# Nestling_2_1_EXB_WIFI_ESP8266EX.net
KiCad netlist of a schematic drawn in Altium Designer
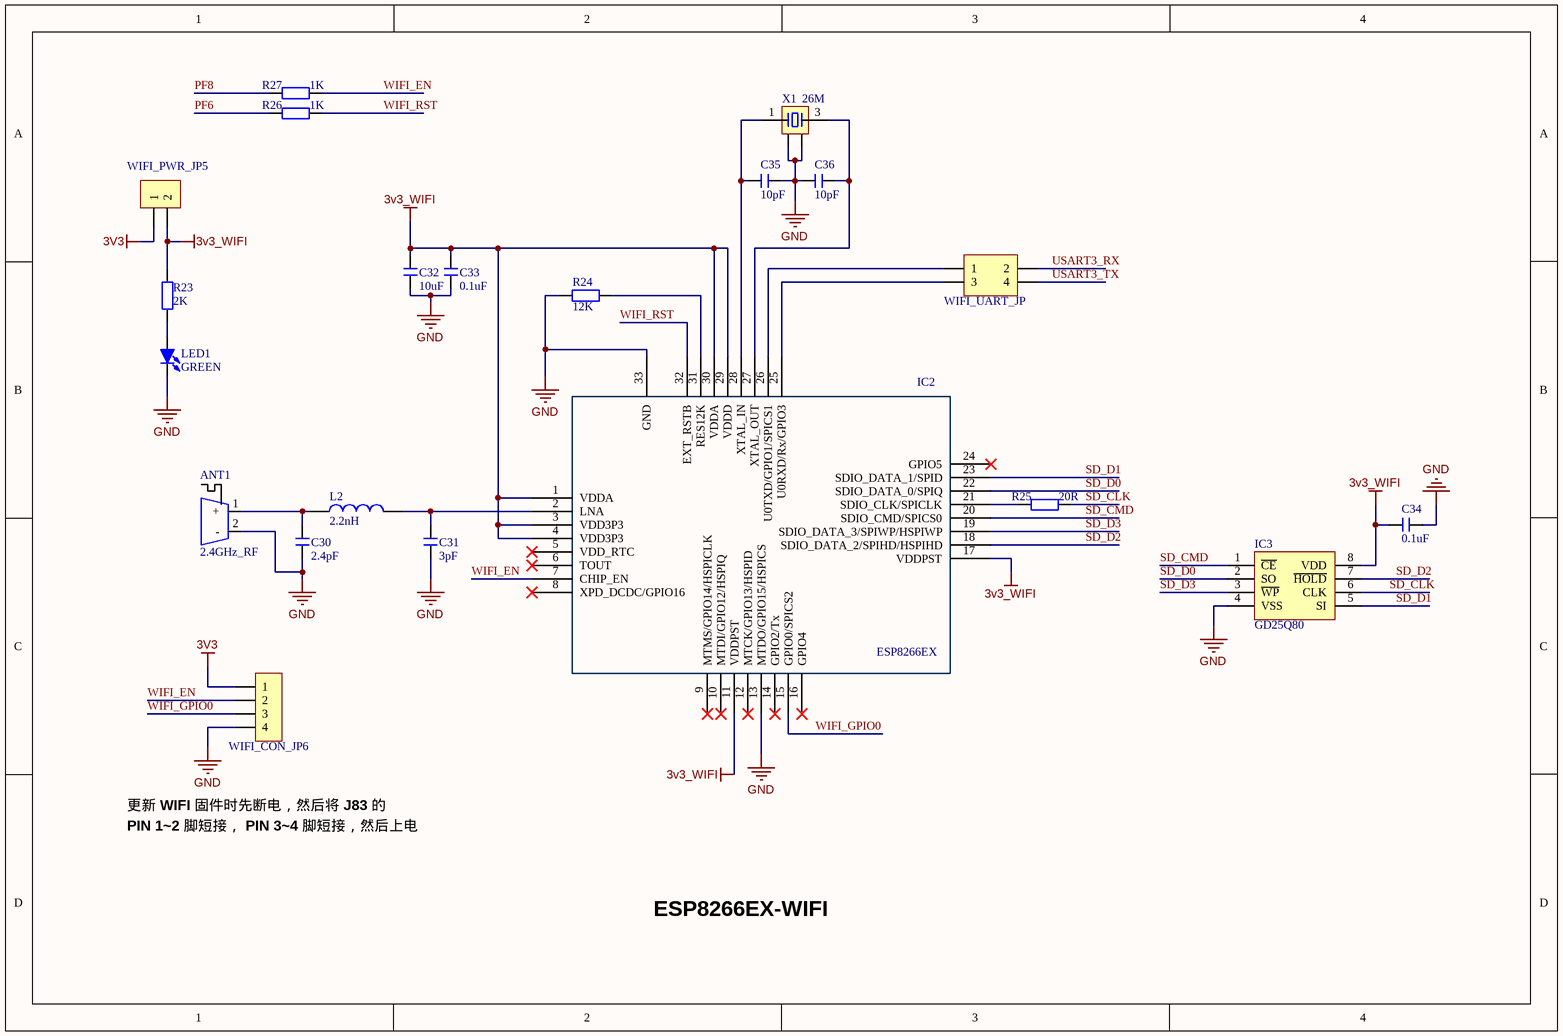
[diagram p0: Nestling_2.1_EXB_WIFI_ESP8266EX.SchDoc]

(export (version "E")
  (design (tool "Eeschema 10.0.6"))
  (components
    (comp (ref "ANT1")
      (value "2.4GHz_RF")
      (footprint "ANT-F-1-2.4G")
      (libsource (lib "altium-import") (part "root_0_2.4GHz_RF_"))
    )
    (comp (ref "C30")
      (value "2.4pF")
      (footprint "C 0603_M")
      (description "无极性贴片电容")
      (fields (field (name "版权归属") "源创客"))
      (libsource (lib "altium-import") (part "root_3_C_"))
    )
    (comp (ref "C31")
      (value "3pF")
      (footprint "C 0603_M")
      (description "无极性贴片电容")
      (fields (field (name "版权归属") "源创客"))
      (libsource (lib "altium-import") (part "root_3_C_"))
    )
    (comp (ref "C32")
      (value "10uF")
      (footprint "C 0603_M")
      (description "无极性贴片电容")
      (fields (field (name "版权归属") "源创客"))
      (libsource (lib "altium-import") (part "root_3_C_"))
    )
    (comp (ref "C33")
      (value "0.1uF")
      (footprint "C 0603_M")
      (description "无极性贴片电容")
      (fields (field (name "版权归属") "源创客"))
      (libsource (lib "altium-import") (part "root_3_C_"))
    )
    (comp (ref "C34")
      (value "0.1uF")
      (footprint "C 0603_M")
      (description "无极性贴片电容")
      (fields (field (name "版权归属") "源创客"))
      (libsource (lib "altium-import") (part "root_0_C_"))
    )
    (comp (ref "C35")
      (value "10pF")
      (footprint "C 0603_M")
      (description "无极性贴片电容")
      (fields (field (name "版权归属") "源创客"))
      (libsource (lib "altium-import") (part "root_2_C_"))
    )
    (comp (ref "C36")
      (value "10pF")
      (footprint "C 0603_M")
      (description "无极性贴片电容")
      (fields (field (name "版权归属") "源创客"))
      (libsource (lib "altium-import") (part "root_2_C_"))
    )
    (comp (ref "IC2")
      (value "ESP8266EX")
      (footprint "QFN32 5x5_L")
      (description "WIFI-芯片")
      (fields (field (name "版权归属") "源创客"))
      (libsource (lib "altium-import") (part "root_0_ESP8266EX_"))
    )
    (comp (ref "IC3")
      (value "GD25Q80")
      (footprint "SOP8W_N")
      (description "外置Flash")
      (fields (field (name "版权归属") "源创客"))
      (libsource (lib "altium-import") (part "root_0_SST25VFxx_"))
    )
    (comp (ref "L2")
      (value "2.2nH")
      (footprint "L 0603")
      (description "小功率贴片电感")
      (fields (field (name "版权归属") "源创客"))
      (libsource (lib "altium-import") (part "root_0_L_"))
    )
    (comp (ref "LED1")
      (value "GREEN")
      (footprint "LED 0603G")
      (description "贴片LED")
      (fields (field (name "版权归属") "源创客"))
      (libsource (lib "altium-import") (part "root_0_LED-SMD_"))
    )
    (comp (ref "R23")
      (value "2K")
      (footprint "R 0603_M")
      (description "Resistor")
      (libsource (lib "") (part "RES_1"))
    )
    (comp (ref "R24")
      (value "12K")
      (footprint "R 0603_M")
      (description "Resistor")
      (libsource (lib "General") (part "RES"))
    )
    (comp (ref "R25")
      (value "20R")
      (footprint "R 0603_M")
      (description "Resistor")
      (libsource (lib "General") (part "RES"))
    )
    (comp (ref "R26")
      (value "1K")
      (footprint "R 0603_M")
      (description "Resistor")
      (libsource (lib "General") (part "RES"))
    )
    (comp (ref "R27")
      (value "1K")
      (footprint "R 0603_M")
      (description "Resistor")
      (libsource (lib "General") (part "RES"))
    )
    (comp (ref "WIFI_CON_JP6")
      (value "HDR-1X4")
      (footprint "HDR2.54-LI-4P")
      (description "4P接插件")
      (fields (field (name "版权归属") "源创客"))
      (libsource (lib "altium-import") (part "root_0_Header 4_"))
    )
    (comp (ref "WIFI_PWR_JP5")
      (value "HDR-1X2")
      (footprint "HDR2.54-LI-2P")
      (description "2P接插件")
      (fields (field (name "版权归属") "源创客"))
      (libsource (lib "altium-import") (part "root_1_Header 2_"))
    )
    (comp (ref "WIFI_UART_JP")
      (value "Header2X2")
      (footprint "HDR2.54-LI-2x2P")
      (description "2*2P接插件")
      (fields (field (name "版权归属") "源创客"))
      (libsource (lib "4.5   - 接插件-脚距2.54") (part "Header 2X2"))
    )
    (comp (ref "X1")
      (value "26M")
      (footprint "OSC 3225-4P")
      (description "4脚无源晶振")
      (fields (field (name "版权归属") "源创客"))
      (libsource (lib "altium-import") (part "root_0_XTAL-4P_"))
    )
  )
  (nets
    (net (code "1") (name "/PF6") (class "Default")
      (node (ref "R26") (pin "2") (pinfunction "2_2") (pintype "passive"))
    )
    (net (code "2") (name "/PF8") (class "Default")
      (node (ref "R27") (pin "2") (pinfunction "2_2") (pintype "passive"))
    )
    (net (code "3") (name "/SD_CLK") (class "Default")
      (node (ref "IC3") (pin "6") (pinfunction "CLK_6") (pintype "passive"))
      (node (ref "R25") (pin "1") (pinfunction "1_1") (pintype "passive"))
    )
    (net (code "4") (name "/SD_CMD") (class "Default")
      (node (ref "IC2") (pin "20") (pinfunction "SDIO_CMD/SPICS0_20") (pintype "passive"))
      (node (ref "IC3") (pin "1") (pinfunction "~{CE}_1") (pintype "passive"))
    )
    (net (code "5") (name "/SD_D0") (class "Default")
      (node (ref "IC2") (pin "22") (pinfunction "SDIO_DATA_0/SPIQ_22") (pintype "passive"))
      (node (ref "IC3") (pin "2") (pinfunction "SO_2") (pintype "passive"))
    )
    (net (code "6") (name "/SD_D1") (class "Default")
      (node (ref "IC2") (pin "23") (pinfunction "SDIO_DATA_1/SPID_23") (pintype "passive"))
      (node (ref "IC3") (pin "5") (pinfunction "SI_5") (pintype "passive"))
    )
    (net (code "7") (name "/SD_D2") (class "Default")
      (node (ref "IC2") (pin "18") (pinfunction "SDIO_DATA_2/SPIHD/HSPIHD_18") (pintype "passive"))
      (node (ref "IC3") (pin "7") (pinfunction "~{HOLD}_7") (pintype "passive"))
    )
    (net (code "8") (name "/SD_D3") (class "Default")
      (node (ref "IC2") (pin "19") (pinfunction "SDIO_DATA_3/SPIWP/HSPIWP_19") (pintype "passive"))
      (node (ref "IC3") (pin "3") (pinfunction "~{WP}_3") (pintype "passive"))
    )
    (net (code "9") (name "/USART3_RX") (class "Default")
      (node (ref "WIFI_UART_JP") (pin "2") (pinfunction "2_2") (pintype "passive"))
    )
    (net (code "10") (name "/USART3_TX") (class "Default")
      (node (ref "WIFI_UART_JP") (pin "4") (pinfunction "4_4") (pintype "passive"))
    )
    (net (code "11") (name "/WIFI_EN") (class "Default")
      (node (ref "IC2") (pin "7") (pinfunction "CHIP_EN_7") (pintype "passive"))
      (node (ref "R27") (pin "1") (pinfunction "1_1") (pintype "passive"))
      (node (ref "WIFI_CON_JP6") (pin "2") (pinfunction "2_2") (pintype "passive"))
    )
    (net (code "12") (name "/WIFI_GPIO0") (class "Default")
      (node (ref "IC2") (pin "15") (pinfunction "GPIO0/SPICS2_15") (pintype "passive"))
      (node (ref "WIFI_CON_JP6") (pin "3") (pinfunction "3_3") (pintype "passive"))
    )
    (net (code "13") (name "/WIFI_RST") (class "Default")
      (node (ref "IC2") (pin "32") (pinfunction "EXT_RSTB_32") (pintype "passive"))
      (node (ref "R26") (pin "1") (pinfunction "1_1") (pintype "passive"))
    )
    (net (code "14") (name "3V3") (class "Default")
      (node (ref "WIFI_CON_JP6") (pin "1") (pinfunction "1_1") (pintype "passive"))
      (node (ref "WIFI_PWR_JP5") (pin "1") (pinfunction "1_1") (pintype "passive"))
    )
    (net (code "15") (name "3v3_WIFI") (class "Default")
      (node (ref "C32") (pin "1") (pinfunction "1_1") (pintype "passive"))
      (node (ref "C33") (pin "1") (pinfunction "1_1") (pintype "passive"))
      (node (ref "C34") (pin "1") (pinfunction "1_1") (pintype "passive"))
      (node (ref "IC2") (pin "1") (pinfunction "VDDA_1") (pintype "passive"))
      (node (ref "IC2") (pin "11") (pinfunction "VDDPST_11") (pintype "passive"))
      (node (ref "IC2") (pin "17") (pinfunction "VDDPST_17") (pintype "passive"))
      (node (ref "IC2") (pin "29") (pinfunction "VDDD_29") (pintype "passive"))
      (node (ref "IC2") (pin "3") (pinfunction "VDD3P3_3") (pintype "passive"))
      (node (ref "IC2") (pin "30") (pinfunction "VDDA_30") (pintype "passive"))
      (node (ref "IC2") (pin "4") (pinfunction "VDD3P3_4") (pintype "passive"))
      (node (ref "IC3") (pin "8") (pinfunction "VDD_8") (pintype "passive"))
      (node (ref "R23") (pin "2") (pinfunction "2_2") (pintype "passive"))
      (node (ref "WIFI_PWR_JP5") (pin "2") (pinfunction "2_2") (pintype "passive"))
    )
    (net (code "16") (name "GND") (class "Default")
      (node (ref "ANT1") (pin "2") (pinfunction "-_2") (pintype "passive"))
      (node (ref "C30") (pin "2") (pinfunction "2_2") (pintype "passive"))
      (node (ref "C31") (pin "2") (pinfunction "2_2") (pintype "passive"))
      (node (ref "C32") (pin "2") (pinfunction "2_2") (pintype "passive"))
      (node (ref "C33") (pin "2") (pinfunction "2_2") (pintype "passive"))
      (node (ref "C34") (pin "2") (pinfunction "2_2") (pintype "passive"))
      (node (ref "C35") (pin "1") (pinfunction "1_1") (pintype "passive"))
      (node (ref "C36") (pin "2") (pinfunction "2_2") (pintype "passive"))
      (node (ref "IC2") (pin "13") (pinfunction "MTDO/GPIO15/HSPICS_13") (pintype "passive"))
      (node (ref "IC2") (pin "33") (pinfunction "GND_33") (pintype "passive"))
      (node (ref "IC3") (pin "4") (pinfunction "VSS_4") (pintype "passive"))
      (node (ref "LED1") (pin "2") (pinfunction "K_2") (pintype "passive"))
      (node (ref "R24") (pin "2") (pinfunction "2_2") (pintype "passive"))
      (node (ref "WIFI_CON_JP6") (pin "4") (pinfunction "4_4") (pintype "passive"))
      (node (ref "X1") (pin "2") (pinfunction "2_2") (pintype "passive"))
      (node (ref "X1") (pin "4") (pinfunction "4_4") (pintype "passive"))
    )
    (net (code "17") (name "Net-(ANT1-+)") (class "Default")
      (node (ref "ANT1") (pin "1") (pinfunction "+_1") (pintype "passive"))
      (node (ref "C30") (pin "1") (pinfunction "1_1") (pintype "passive"))
      (node (ref "L2") (pin "1") (pinfunction "1_1") (pintype "passive"))
    )
    (net (code "18") (name "Net-(IC2-LNA)") (class "Default")
      (node (ref "C31") (pin "1") (pinfunction "1_1") (pintype "passive"))
      (node (ref "IC2") (pin "2") (pinfunction "LNA_2") (pintype "passive"))
      (node (ref "L2") (pin "2") (pinfunction "2_2") (pintype "passive"))
    )
    (net (code "19") (name "Net-(IC2-RES12K)") (class "Default")
      (node (ref "IC2") (pin "31") (pinfunction "RES12K_31") (pintype "passive"))
      (node (ref "R24") (pin "1") (pinfunction "1_1") (pintype "passive"))
    )
    (net (code "20") (name "Net-(IC2-SDIO_CLK{slash}SPICLK)") (class "Default")
      (node (ref "IC2") (pin "21") (pinfunction "SDIO_CLK/SPICLK_21") (pintype "passive"))
      (node (ref "R25") (pin "2") (pinfunction "2_2") (pintype "passive"))
    )
    (net (code "21") (name "Net-(IC2-U0RXD{slash}Rx{slash}GPIO3)") (class "Default")
      (node (ref "IC2") (pin "25") (pinfunction "U0RXD/Rx/GPIO3_25") (pintype "passive"))
      (node (ref "WIFI_UART_JP") (pin "3") (pinfunction "3_3") (pintype "passive"))
    )
    (net (code "22") (name "Net-(IC2-U0TXD{slash}GPIO1{slash}SPICS1)") (class "Default")
      (node (ref "IC2") (pin "26") (pinfunction "U0TXD/GPIO1/SPICS1_26") (pintype "passive"))
      (node (ref "WIFI_UART_JP") (pin "1") (pinfunction "1_1") (pintype "passive"))
    )
    (net (code "23") (name "Net-(IC2-XTAL_IN)") (class "Default")
      (node (ref "C35") (pin "2") (pinfunction "2_2") (pintype "passive"))
      (node (ref "IC2") (pin "28") (pinfunction "XTAL_IN_28") (pintype "passive"))
      (node (ref "X1") (pin "1") (pinfunction "1_1") (pintype "passive"))
    )
    (net (code "24") (name "Net-(IC2-XTAL_OUT)") (class "Default")
      (node (ref "C36") (pin "1") (pinfunction "1_1") (pintype "passive"))
      (node (ref "IC2") (pin "27") (pinfunction "XTAL_OUT_27") (pintype "passive"))
      (node (ref "X1") (pin "3") (pinfunction "3_3") (pintype "passive"))
    )
    (net (code "25") (name "Net-(LED1-A)") (class "Default")
      (node (ref "LED1") (pin "1") (pinfunction "A_1") (pintype "passive"))
      (node (ref "R23") (pin "1") (pinfunction "1_1") (pintype "passive"))
    )
    (net (code "26") (name "unconnected-(IC2-GPIO2{slash}Tx-Pad14)") (class "Default")
      (node (ref "IC2") (pin "14") (pinfunction "GPIO2/Tx_14") (pintype "passive+no_connect"))
    )
    (net (code "27") (name "unconnected-(IC2-GPIO4-Pad16)") (class "Default")
      (node (ref "IC2") (pin "16") (pinfunction "GPIO4_16") (pintype "passive+no_connect"))
    )
    (net (code "28") (name "unconnected-(IC2-GPIO5-Pad24)") (class "Default")
      (node (ref "IC2") (pin "24") (pinfunction "GPIO5_24") (pintype "passive+no_connect"))
    )
    (net (code "29") (name "unconnected-(IC2-MTCK{slash}GPIO13{slash}HSPID-Pad12)") (class "Default")
      (node (ref "IC2") (pin "12") (pinfunction "MTCK/GPIO13/HSPID_12") (pintype "passive+no_connect"))
    )
    (net (code "30") (name "unconnected-(IC2-MTDI{slash}GPIO12{slash}HSPIQ-Pad10)") (class "Default")
      (node (ref "IC2") (pin "10") (pinfunction "MTDI/GPIO12/HSPIQ_10") (pintype "passive+no_connect"))
    )
    (net (code "31") (name "unconnected-(IC2-MTMS{slash}GPIO14{slash}HSPICLK-Pad9)") (class "Default")
      (node (ref "IC2") (pin "9") (pinfunction "MTMS/GPIO14/HSPICLK_9") (pintype "passive+no_connect"))
    )
    (net (code "32") (name "unconnected-(IC2-TOUT-Pad6)") (class "Default")
      (node (ref "IC2") (pin "6") (pinfunction "TOUT_6") (pintype "passive+no_connect"))
    )
    (net (code "33") (name "unconnected-(IC2-VDD_RTC-Pad5)") (class "Default")
      (node (ref "IC2") (pin "5") (pinfunction "VDD_RTC_5") (pintype "passive+no_connect"))
    )
    (net (code "34") (name "unconnected-(IC2-XPD_DCDC{slash}GPIO16-Pad8)") (class "Default")
      (node (ref "IC2") (pin "8") (pinfunction "XPD_DCDC/GPIO16_8") (pintype "passive+no_connect"))
    )
  )
)
